# YogiBear.net
KiCad netlist of a schematic drawn in EAGLE
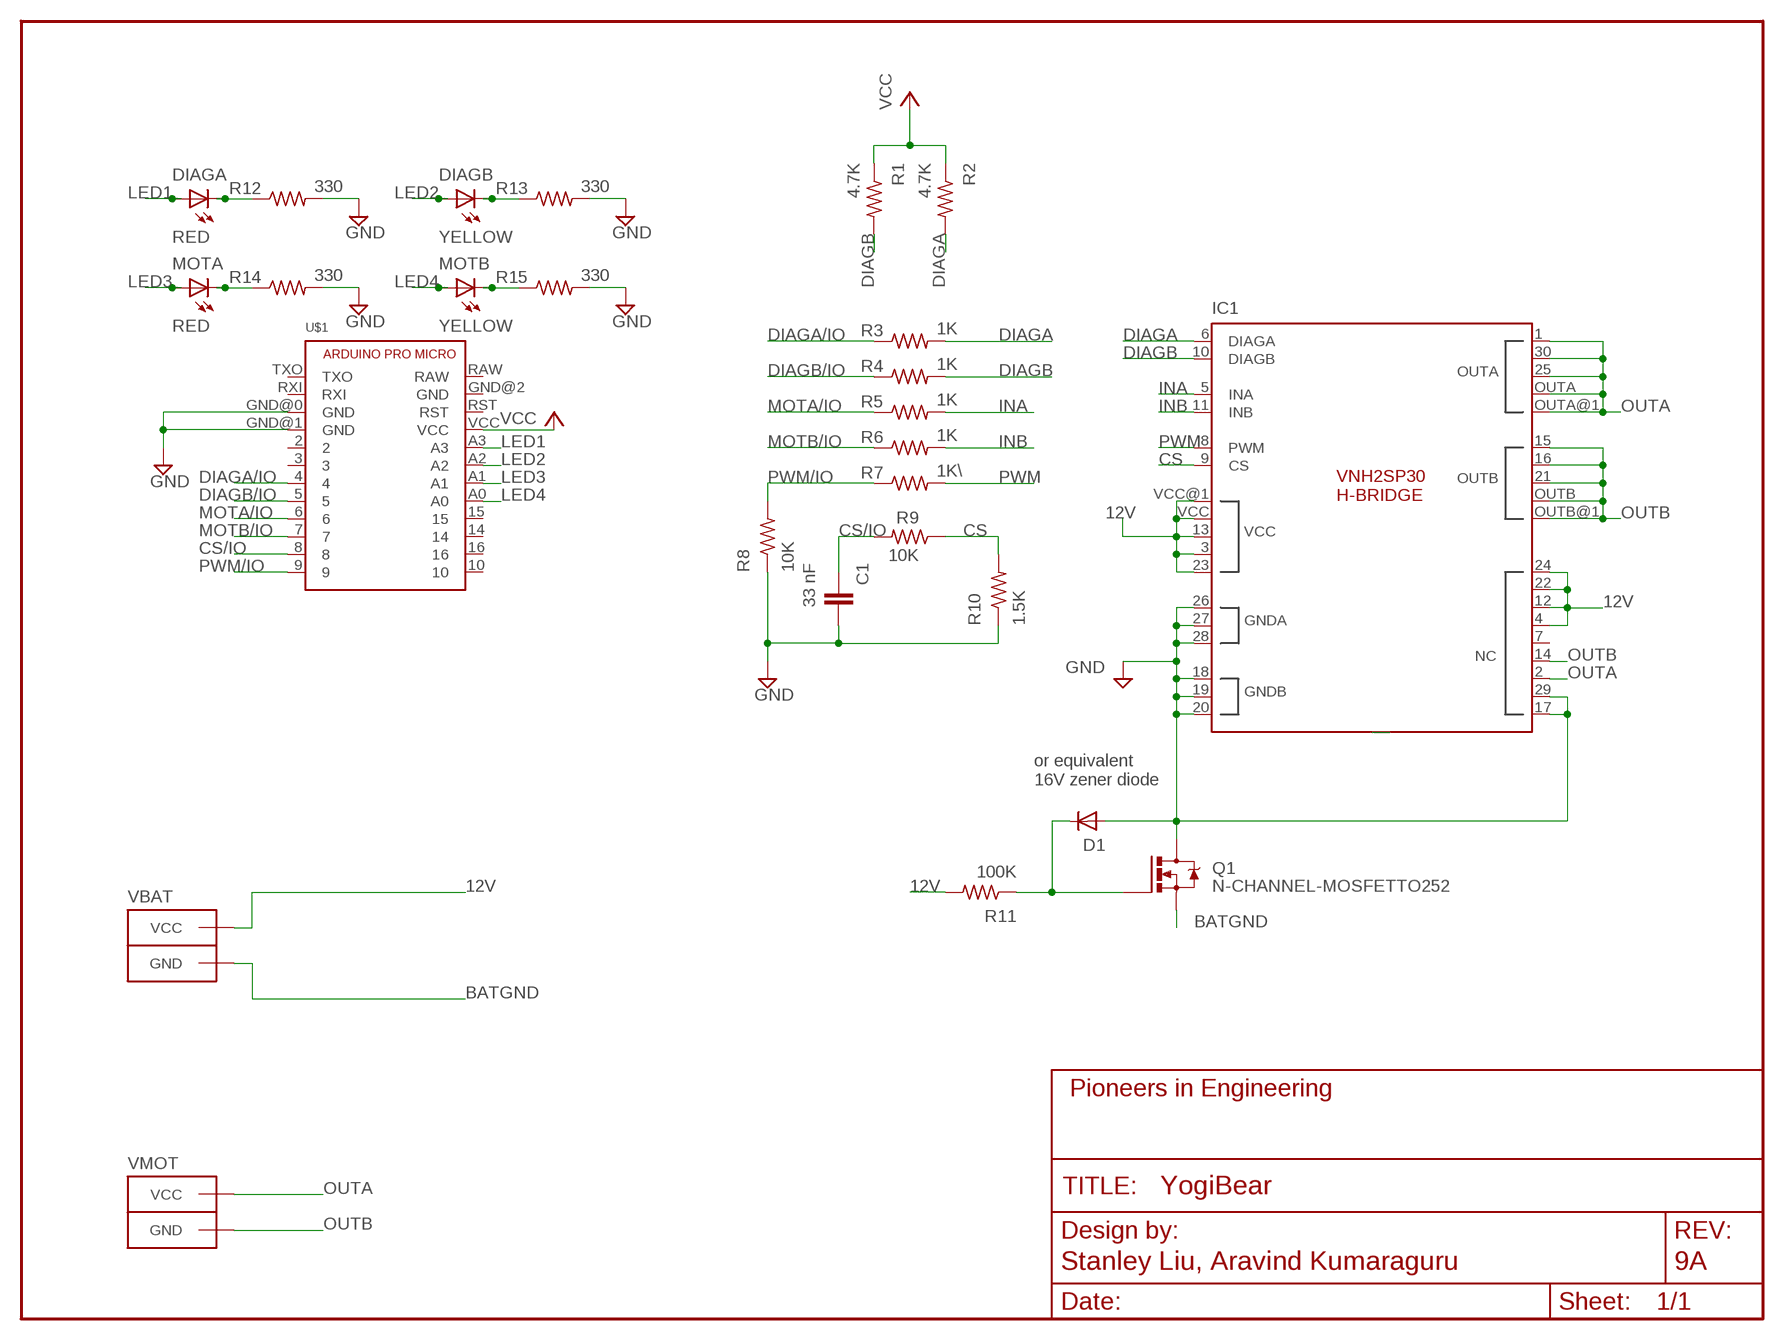
[diagram p0: schematic, sheet 1]

(export (version "E")
  (design (tool "Eeschema 10.0.6"))
  (components
    (comp (ref "C1")
      (value "33 nF")
      (footprint "eagle-import:0603-CAP")
      (libsource (lib "eagle-import") (part "CAP0603-CAP"))
    )
    (comp (ref "D1")
      (value "DIODESMA-ALT")
      (footprint "eagle-import:SMA-DIODE_ALT")
      (libsource (lib "eagle-import") (part "DIODESMA-ALT"))
    )
    (comp (ref "DIAGA")
      (value "RED")
      (footprint "eagle-import:LED-0603")
      (libsource (lib "eagle-import") (part "LED0603"))
    )
    (comp (ref "DIAGB")
      (value "YELLOW")
      (footprint "eagle-import:LED-0603")
      (libsource (lib "eagle-import") (part "LED0603"))
    )
    (comp (ref "IC1")
      (value "VNH2SP30")
      (footprint "eagle-import:VNH2SP30")
      (fields (field (name "MPN") "VNH3SP30-E"))
      (libsource (lib "eagle-import") (part "VNH2SP30"))
    )
    (comp (ref "MOTA")
      (value "RED")
      (footprint "eagle-import:LED-0603")
      (libsource (lib "eagle-import") (part "LED0603"))
    )
    (comp (ref "MOTB")
      (value "YELLOW")
      (footprint "eagle-import:LED-0603")
      (libsource (lib "eagle-import") (part "LED0603"))
    )
    (comp (ref "Q1")
      (value "N-CHANNEL-MOSFETTO252")
      (footprint "eagle-import:TO252")
      (libsource (lib "eagle-import") (part "N-CHANNEL-MOSFETTO252"))
    )
    (comp (ref "R1")
      (value "4.7K")
      (footprint "eagle-import:R0603")
      (libsource (lib "eagle-import") (part "R-US_R0603"))
    )
    (comp (ref "R2")
      (value "4.7K")
      (footprint "eagle-import:R0603")
      (libsource (lib "eagle-import") (part "R-US_R0603"))
    )
    (comp (ref "R3")
      (value "1K")
      (footprint "eagle-import:R0603")
      (libsource (lib "eagle-import") (part "R-US_R0603"))
    )
    (comp (ref "R4")
      (value "1K")
      (footprint "eagle-import:R0603")
      (libsource (lib "eagle-import") (part "R-US_R0603"))
    )
    (comp (ref "R5")
      (value "1K")
      (footprint "eagle-import:R0603")
      (libsource (lib "eagle-import") (part "R-US_R0603"))
    )
    (comp (ref "R6")
      (value "1K")
      (footprint "eagle-import:R0603")
      (libsource (lib "eagle-import") (part "R-US_R0603"))
    )
    (comp (ref "R7")
      (value "1K\\")
      (footprint "eagle-import:R0603")
      (libsource (lib "eagle-import") (part "R-US_R0603"))
    )
    (comp (ref "R8")
      (value "10K")
      (footprint "eagle-import:R0603")
      (libsource (lib "eagle-import") (part "R-US_R0603"))
    )
    (comp (ref "R9")
      (value "10K")
      (footprint "eagle-import:R0603")
      (libsource (lib "eagle-import") (part "R-US_R0603"))
    )
    (comp (ref "R10")
      (value "1.5K")
      (footprint "eagle-import:R0603")
      (libsource (lib "eagle-import") (part "R-US_R0603"))
    )
    (comp (ref "R11")
      (value "100K")
      (footprint "eagle-import:R0603")
      (libsource (lib "eagle-import") (part "R-US_R0603"))
    )
    (comp (ref "R12")
      (value "330")
      (footprint "eagle-import:R0603")
      (libsource (lib "eagle-import") (part "R-US_R0603"))
    )
    (comp (ref "R13")
      (value "330")
      (footprint "eagle-import:R0603")
      (libsource (lib "eagle-import") (part "R-US_R0603"))
    )
    (comp (ref "R14")
      (value "330")
      (footprint "eagle-import:R0603")
      (libsource (lib "eagle-import") (part "R-US_R0603"))
    )
    (comp (ref "R15")
      (value "330")
      (footprint "eagle-import:R0603")
      (libsource (lib "eagle-import") (part "R-US_R0603"))
    )
    (comp (ref "U$1")
      (value "ARDUINO_PRO_MICRO")
      (footprint "eagle-import:ARDUINO_PRO_MICRO")
      (libsource (lib "eagle-import") (part "ARDUINO_PRO_MICRO"))
    )
    (comp (ref "VBAT")
      (value "ANDERSONVERTICAL")
      (footprint "eagle-import:ANDERSON_VERTICAL")
      (libsource (lib "eagle-import") (part "ANDERSONVERTICAL"))
    )
    (comp (ref "VMOT")
      (value "ANDERSONVERTICAL")
      (footprint "eagle-import:ANDERSON_VERTICAL")
      (libsource (lib "eagle-import") (part "ANDERSONVERTICAL"))
    )
  )
  (nets
    (net (code "1") (name "/12V") (class "Default")
      (node (ref "IC1") (pin "12") (pinfunction "NC6_12") (pintype "power_in"))
      (node (ref "IC1") (pin "13") (pinfunction "VCC_13") (pintype "power_in"))
      (node (ref "IC1") (pin "22") (pinfunction "NC7_22") (pintype "power_in"))
      (node (ref "IC1") (pin "23") (pinfunction "VCC_23") (pintype "power_in"))
      (node (ref "IC1") (pin "24") (pinfunction "NC8_24") (pintype "power_in"))
      (node (ref "IC1") (pin "3") (pinfunction "VCC_3") (pintype "power_in"))
      (node (ref "IC1") (pin "4") (pinfunction "NC5_4") (pintype "power_in"))
      (node (ref "IC1") (pin "VCC") (pinfunction "VCC_VCC") (pintype "power_in"))
      (node (ref "IC1") (pin "VCC@1") (pinfunction "VCC_VCC@1") (pintype "power_in"))
      (node (ref "R11") (pin "2") (pinfunction "2_2") (pintype "passive"))
      (node (ref "VBAT") (pin "PIN2") (pinfunction "VCC_PIN2") (pintype "bidirectional"))
    )
    (net (code "2") (name "/BATGND") (class "Default")
      (node (ref "Q1") (pin "2") (pinfunction "S_2") (pintype "passive"))
      (node (ref "VBAT") (pin "PIN1") (pinfunction "GND_PIN1") (pintype "bidirectional"))
    )
    (net (code "3") (name "/CS") (class "Default")
      (node (ref "IC1") (pin "9") (pinfunction "CS_9") (pintype "input"))
      (node (ref "R10") (pin "2") (pinfunction "2_2") (pintype "passive"))
      (node (ref "R9") (pin "1") (pinfunction "1_1") (pintype "passive"))
    )
    (net (code "4") (name "/CS{slash}IO") (class "Default")
      (node (ref "C1") (pin "1") (pinfunction "1_1") (pintype "passive"))
      (node (ref "R9") (pin "2") (pinfunction "2_2") (pintype "passive"))
      (node (ref "U$1") (pin "8") (pinfunction "8_8") (pintype "bidirectional"))
    )
    (net (code "5") (name "/DIAGA") (class "Default")
      (node (ref "IC1") (pin "6") (pinfunction "DIAGA_6") (pintype "open_collector"))
      (node (ref "R2") (pin "2") (pinfunction "2_2") (pintype "passive"))
      (node (ref "R3") (pin "2") (pinfunction "2_2") (pintype "passive"))
    )
    (net (code "6") (name "/DIAGA{slash}IO") (class "Default")
      (node (ref "R3") (pin "1") (pinfunction "1_1") (pintype "passive"))
      (node (ref "U$1") (pin "4") (pinfunction "4_4") (pintype "bidirectional"))
    )
    (net (code "7") (name "/DIAGB") (class "Default")
      (node (ref "IC1") (pin "10") (pinfunction "DIAGB_10") (pintype "open_collector"))
      (node (ref "R1") (pin "2") (pinfunction "2_2") (pintype "passive"))
      (node (ref "R4") (pin "2") (pinfunction "2_2") (pintype "passive"))
    )
    (net (code "8") (name "/DIAGB{slash}IO") (class "Default")
      (node (ref "R4") (pin "1") (pinfunction "1_1") (pintype "passive"))
      (node (ref "U$1") (pin "5") (pinfunction "5_5") (pintype "bidirectional"))
    )
    (net (code "9") (name "/INA") (class "Default")
      (node (ref "IC1") (pin "5") (pinfunction "INA_5") (pintype "input"))
      (node (ref "R5") (pin "2") (pinfunction "2_2") (pintype "passive"))
    )
    (net (code "10") (name "/INB") (class "Default")
      (node (ref "IC1") (pin "11") (pinfunction "INB_11") (pintype "input"))
      (node (ref "R6") (pin "2") (pinfunction "2_2") (pintype "passive"))
    )
    (net (code "11") (name "/LED1") (class "Default")
      (node (ref "DIAGA") (pin "A") (pinfunction "A_A") (pintype "passive"))
      (node (ref "U$1") (pin "A3") (pinfunction "A3_A3") (pintype "bidirectional"))
    )
    (net (code "12") (name "/LED2") (class "Default")
      (node (ref "DIAGB") (pin "A") (pinfunction "A_A") (pintype "passive"))
      (node (ref "U$1") (pin "A2") (pinfunction "A2_A2") (pintype "bidirectional"))
    )
    (net (code "13") (name "/LED3") (class "Default")
      (node (ref "MOTA") (pin "A") (pinfunction "A_A") (pintype "passive"))
      (node (ref "U$1") (pin "A1") (pinfunction "A1_A1") (pintype "bidirectional"))
    )
    (net (code "14") (name "/LED4") (class "Default")
      (node (ref "MOTB") (pin "A") (pinfunction "A_A") (pintype "passive"))
      (node (ref "U$1") (pin "A0") (pinfunction "A0_A0") (pintype "bidirectional"))
    )
    (net (code "15") (name "/MOTA{slash}IO") (class "Default")
      (node (ref "R5") (pin "1") (pinfunction "1_1") (pintype "passive"))
      (node (ref "U$1") (pin "6") (pinfunction "6_6") (pintype "bidirectional"))
    )
    (net (code "16") (name "/MOTB{slash}IO") (class "Default")
      (node (ref "R6") (pin "1") (pinfunction "1_1") (pintype "passive"))
      (node (ref "U$1") (pin "7") (pinfunction "7_7") (pintype "bidirectional"))
    )
    (net (code "17") (name "/NC4") (class "Default")
      (node (ref "IC1") (pin "7") (pinfunction "NC4_7") (pintype "power_in"))
    )
    (net (code "18") (name "/OUTA") (class "Default")
      (node (ref "IC1") (pin "1") (pinfunction "OUTA_1") (pintype "output"))
      (node (ref "IC1") (pin "2") (pinfunction "NC2_2") (pintype "power_in"))
      (node (ref "IC1") (pin "25") (pinfunction "OUTA_25") (pintype "passive"))
      (node (ref "IC1") (pin "30") (pinfunction "OUTA_30") (pintype "passive"))
      (node (ref "IC1") (pin "OUTA") (pinfunction "OUTA_OUTA") (pintype "passive"))
      (node (ref "IC1") (pin "OUTA@1") (pinfunction "OUTA_OUTA@1") (pintype "passive"))
      (node (ref "VMOT") (pin "PIN2") (pinfunction "VCC_PIN2") (pintype "bidirectional"))
    )
    (net (code "19") (name "/OUTB") (class "Default")
      (node (ref "IC1") (pin "14") (pinfunction "NC3_14") (pintype "power_in"))
      (node (ref "IC1") (pin "15") (pinfunction "OUTB_15") (pintype "output"))
      (node (ref "IC1") (pin "16") (pinfunction "OUTB_16") (pintype "passive"))
      (node (ref "IC1") (pin "21") (pinfunction "OUTB_21") (pintype "passive"))
      (node (ref "IC1") (pin "OUTB") (pinfunction "OUTB_OUTB") (pintype "passive"))
      (node (ref "IC1") (pin "OUTB@1") (pinfunction "OUTB_OUTB@1") (pintype "passive"))
      (node (ref "VMOT") (pin "PIN1") (pinfunction "GND_PIN1") (pintype "bidirectional"))
    )
    (net (code "20") (name "/PWM") (class "Default")
      (node (ref "IC1") (pin "8") (pinfunction "PWM_8") (pintype "input"))
      (node (ref "R7") (pin "2") (pinfunction "2_2") (pintype "passive"))
    )
    (net (code "21") (name "/PWM{slash}IO") (class "Default")
      (node (ref "R7") (pin "1") (pinfunction "1_1") (pintype "passive"))
      (node (ref "R8") (pin "2") (pinfunction "2_2") (pintype "passive"))
      (node (ref "U$1") (pin "9") (pinfunction "9_9") (pintype "bidirectional"))
    )
    (net (code "22") (name "GND") (class "Default")
      (node (ref "C1") (pin "2") (pinfunction "2_2") (pintype "passive"))
      (node (ref "D1") (pin "A") (pinfunction "A_A") (pintype "passive"))
      (node (ref "IC1") (pin "17") (pinfunction "NC_17") (pintype "power_in"))
      (node (ref "IC1") (pin "18") (pinfunction "GNDB_18") (pintype "power_in"))
      (node (ref "IC1") (pin "19") (pinfunction "GNDB_19") (pintype "power_in"))
      (node (ref "IC1") (pin "20") (pinfunction "GNDB_20") (pintype "power_in"))
      (node (ref "IC1") (pin "26") (pinfunction "GNDA_26") (pintype "power_in"))
      (node (ref "IC1") (pin "27") (pinfunction "GNDA_27") (pintype "power_in"))
      (node (ref "IC1") (pin "28") (pinfunction "GNDA_28") (pintype "power_in"))
      (node (ref "IC1") (pin "29") (pinfunction "NC1_29") (pintype "power_in"))
      (node (ref "Q1") (pin "3") (pinfunction "D_3") (pintype "passive"))
      (node (ref "R10") (pin "1") (pinfunction "1_1") (pintype "passive"))
      (node (ref "R12") (pin "2") (pinfunction "2_2") (pintype "passive"))
      (node (ref "R13") (pin "2") (pinfunction "2_2") (pintype "passive"))
      (node (ref "R14") (pin "2") (pinfunction "2_2") (pintype "passive"))
      (node (ref "R15") (pin "2") (pinfunction "2_2") (pintype "passive"))
      (node (ref "R8") (pin "1") (pinfunction "1_1") (pintype "passive"))
      (node (ref "U$1") (pin "GND@0") (pinfunction "GND_GND@0") (pintype "bidirectional"))
      (node (ref "U$1") (pin "GND@1") (pinfunction "GND_GND@1") (pintype "bidirectional"))
    )
    (net (code "23") (name "Net-(DIAGA-PadC)") (class "Default")
      (node (ref "DIAGA") (pin "C") (pinfunction "C_C") (pintype "passive"))
      (node (ref "R12") (pin "1") (pinfunction "1_1") (pintype "passive"))
    )
    (net (code "24") (name "Net-(DIAGB-PadC)") (class "Default")
      (node (ref "DIAGB") (pin "C") (pinfunction "C_C") (pintype "passive"))
      (node (ref "R13") (pin "1") (pinfunction "1_1") (pintype "passive"))
    )
    (net (code "25") (name "Net-(MOTA-PadC)") (class "Default")
      (node (ref "MOTA") (pin "C") (pinfunction "C_C") (pintype "passive"))
      (node (ref "R14") (pin "1") (pinfunction "1_1") (pintype "passive"))
    )
    (net (code "26") (name "Net-(MOTB-PadC)") (class "Default")
      (node (ref "MOTB") (pin "C") (pinfunction "C_C") (pintype "passive"))
      (node (ref "R15") (pin "1") (pinfunction "1_1") (pintype "passive"))
    )
    (net (code "27") (name "Net-(Q1-G)") (class "Default")
      (node (ref "D1") (pin "C") (pinfunction "C_C") (pintype "passive"))
      (node (ref "Q1") (pin "1") (pinfunction "G_1") (pintype "passive"))
      (node (ref "R11") (pin "1") (pinfunction "1_1") (pintype "passive"))
    )
    (net (code "28") (name "VCC") (class "Default")
      (node (ref "R1") (pin "1") (pinfunction "1_1") (pintype "passive"))
      (node (ref "R2") (pin "1") (pinfunction "1_1") (pintype "passive"))
      (node (ref "U$1") (pin "VCC") (pinfunction "VCC_VCC") (pintype "bidirectional"))
    )
    (net (code "29") (name "unconnected-(U$1-GND-PadGND@2)") (class "Default")
      (node (ref "U$1") (pin "GND@2") (pinfunction "GND_GND@2") (pintype "bidirectional"))
    )
    (net (code "30") (name "unconnected-(U$1-Pad2)") (class "Default")
      (node (ref "U$1") (pin "2") (pinfunction "2_2") (pintype "bidirectional"))
    )
    (net (code "31") (name "unconnected-(U$1-Pad3)") (class "Default")
      (node (ref "U$1") (pin "3") (pinfunction "3_3") (pintype "bidirectional"))
    )
    (net (code "32") (name "unconnected-(U$1-Pad10)") (class "Default")
      (node (ref "U$1") (pin "10") (pinfunction "10_10") (pintype "bidirectional"))
    )
    (net (code "33") (name "unconnected-(U$1-Pad14)") (class "Default")
      (node (ref "U$1") (pin "14") (pinfunction "14_14") (pintype "bidirectional"))
    )
    (net (code "34") (name "unconnected-(U$1-Pad15)") (class "Default")
      (node (ref "U$1") (pin "15") (pinfunction "15_15") (pintype "bidirectional"))
    )
    (net (code "35") (name "unconnected-(U$1-Pad16)") (class "Default")
      (node (ref "U$1") (pin "16") (pinfunction "16_16") (pintype "bidirectional"))
    )
    (net (code "36") (name "unconnected-(U$1-PadRAW)") (class "Default")
      (node (ref "U$1") (pin "RAW") (pinfunction "RAW_RAW") (pintype "bidirectional"))
    )
    (net (code "37") (name "unconnected-(U$1-PadRST)") (class "Default")
      (node (ref "U$1") (pin "RST") (pinfunction "RST_RST") (pintype "bidirectional"))
    )
    (net (code "38") (name "unconnected-(U$1-PadRXI)") (class "Default")
      (node (ref "U$1") (pin "RXI") (pinfunction "RXI_RXI") (pintype "bidirectional"))
    )
    (net (code "39") (name "unconnected-(U$1-PadTXO)") (class "Default")
      (node (ref "U$1") (pin "TXO") (pinfunction "TXO_TXO") (pintype "bidirectional"))
    )
  )
)
